# nRF_Board.net
KiCad netlist of a schematic drawn in Altium Designer
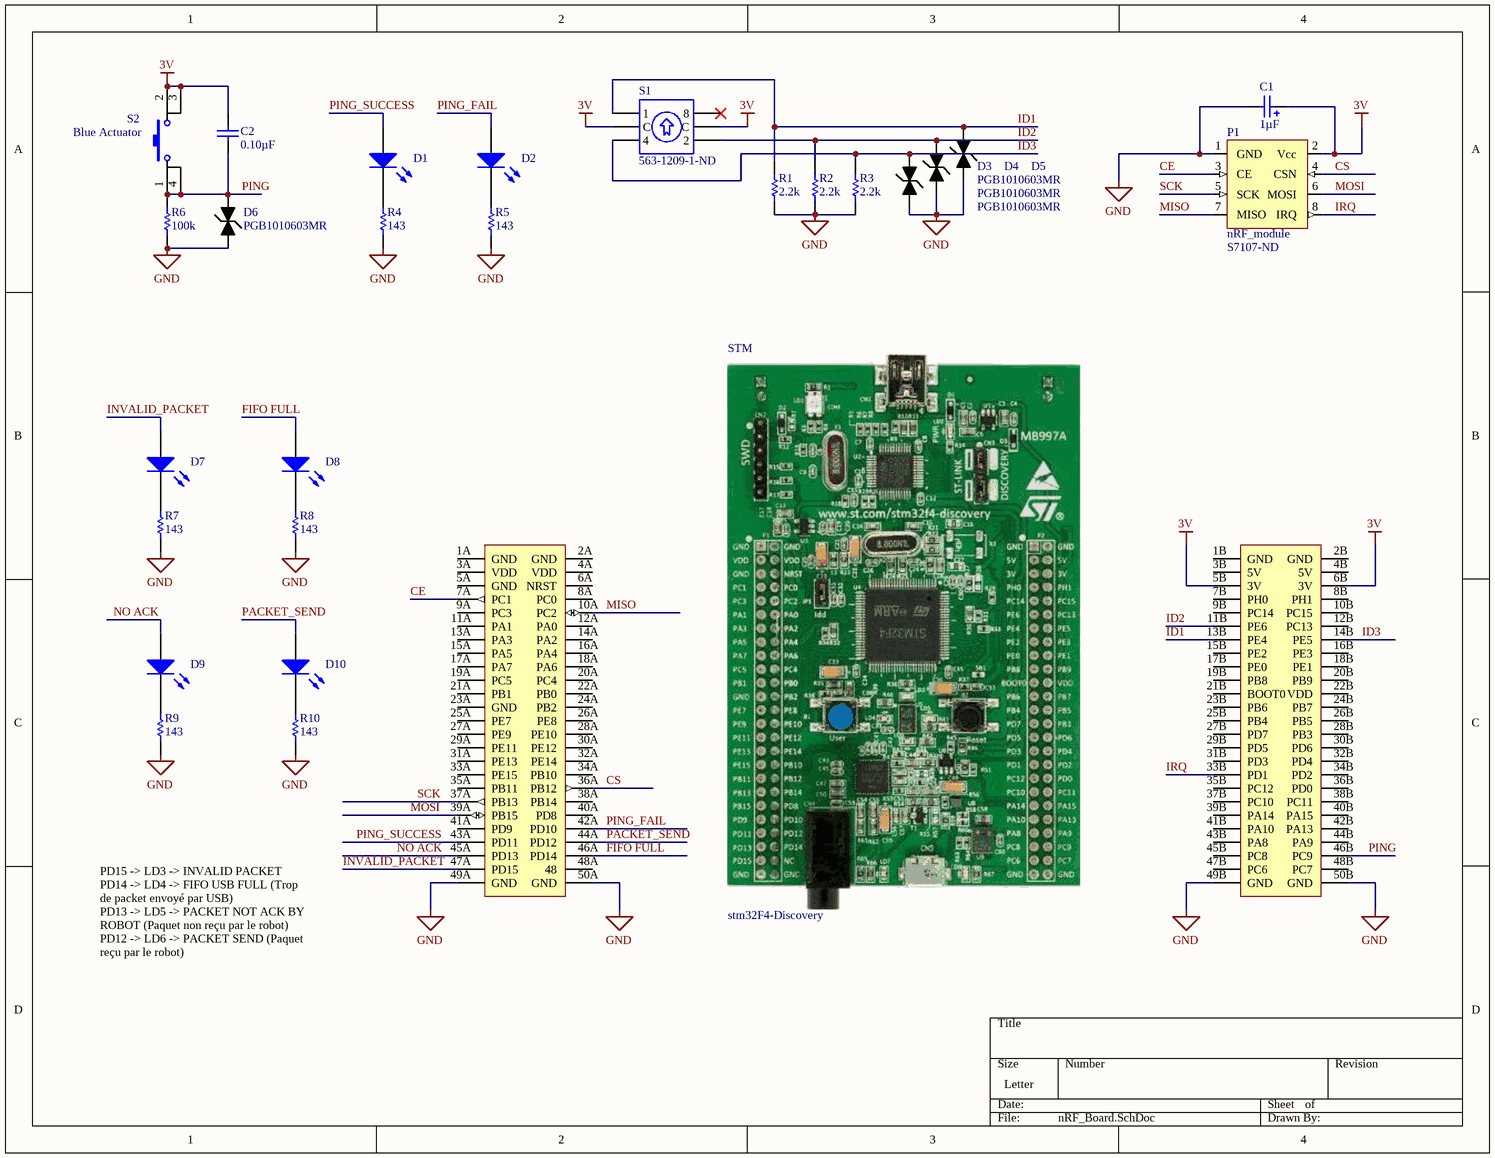
[diagram p0: nRF_Board.SchDoc]

(export (version "E")
  (design (tool "Eeschema 10.0.6"))
  (components
    (comp (ref "C1")
      (value "865060640001")
      (footprint "CAP 4.3x4.3mm")
      (description "CAP 1 UF 20% 50 V")
      (fields
        (field (name "MANUFACTURER") "Wurth Electronics Inc")
        (field (name "TOLERANCE") "±20%")
        (field (name "CAPACITANCE") "1µF")
      )
      (libsource (lib "ResCap") (part "865060640001"))
    )
    (comp (ref "C2")
      (value "CL10B104KB8SFNC")
      (footprint "0603")
      (description "CAP CER 0.1UF 50V X7R 0603")
      (fields
        (field (name "MANUFACTURER") "Samsung Electro-Mechanics America, Inc.")
        (field (name "TOLERANCE") "±10%")
        (field (name "CAPACITANCE") "0.10µF")
      )
      (libsource (lib "ResCap") (part "CL10B104KB8SFNC"))
    )
    (comp (ref "D1")
      (value "LG R971-KN-1")
      (footprint "0805")
      (description "LED GREEN DIFFUSED 0805 SMD")
      (fields (field (name "MANUFACTURER") "OSRAM Opto Semiconductors Inc."))
      (libsource (lib "MainBoard") (part "LG R971-KN-1"))
    )
    (comp (ref "D2")
      (value "LG R971-KN-1")
      (footprint "0805")
      (description "LED GREEN DIFFUSED 0805 SMD")
      (fields (field (name "MANUFACTURER") "OSRAM Opto Semiconductors Inc."))
      (libsource (lib "MainBoard") (part "LG R971-KN-1"))
    )
    (comp (ref "D3")
      (value "PGB1010603MR")
      (footprint "0603")
      (description "TVS DIODE 24VWM 150VC 0603")
      (libsource (lib "MainBoard") (part "PGB1010603MR"))
    )
    (comp (ref "D4")
      (value "PGB1010603MR")
      (footprint "0603")
      (description "TVS DIODE 24VWM 150VC 0603")
      (libsource (lib "MainBoard") (part "PGB1010603MR"))
    )
    (comp (ref "D5")
      (value "PGB1010603MR")
      (footprint "0603")
      (description "TVS DIODE 24VWM 150VC 0603")
      (libsource (lib "MainBoard") (part "PGB1010603MR"))
    )
    (comp (ref "D6")
      (value "PGB1010603MR")
      (footprint "0603")
      (description "TVS DIODE 24VWM 150VC 0603")
      (libsource (lib "MainBoard") (part "PGB1010603MR"))
    )
    (comp (ref "D7")
      (value "LG R971-KN-1")
      (footprint "0805")
      (description "LED GREEN DIFFUSED 0805 SMD")
      (fields (field (name "MANUFACTURER") "OSRAM Opto Semiconductors Inc."))
      (libsource (lib "MainBoard") (part "LG R971-KN-1"))
    )
    (comp (ref "D8")
      (value "LG R971-KN-1")
      (footprint "0805")
      (description "LED GREEN DIFFUSED 0805 SMD")
      (fields (field (name "MANUFACTURER") "OSRAM Opto Semiconductors Inc."))
      (libsource (lib "MainBoard") (part "LG R971-KN-1"))
    )
    (comp (ref "D9")
      (value "LG R971-KN-1")
      (footprint "0805")
      (description "LED GREEN DIFFUSED 0805 SMD")
      (fields (field (name "MANUFACTURER") "OSRAM Opto Semiconductors Inc."))
      (libsource (lib "MainBoard") (part "LG R971-KN-1"))
    )
    (comp (ref "D10")
      (value "LG R971-KN-1")
      (footprint "0805")
      (description "LED GREEN DIFFUSED 0805 SMD")
      (fields (field (name "MANUFACTURER") "OSRAM Opto Semiconductors Inc."))
      (libsource (lib "MainBoard") (part "LG R971-KN-1"))
    )
    (comp (ref "P1")
      (value "nRF_module")
      (footprint "nRF_connector")
      (description "2x4 100mil header")
      (fields (field (name "SUPPLIER PART NUMBER 1") "S7107-ND"))
      (libsource (lib "MainBoard") (part "nRF_module"))
    )
    (comp (ref "R1")
      (value "RC0603FR-072K2L")
      (footprint "0603")
      (description "RES SMD 2.2K OHM 1% 1/10W 0603")
      (fields
        (field (name "MANUFACTURER") "Yageo")
        (field (name "TOLERANCE") "±1%")
        (field (name "RESISTANCE (OHMS)") "2.2k")
      )
      (libsource (lib "ResCap") (part "RC0603FR-072K2L"))
    )
    (comp (ref "R2")
      (value "RC0603FR-072K2L")
      (footprint "0603")
      (description "RES SMD 2.2K OHM 1% 1/10W 0603")
      (fields
        (field (name "MANUFACTURER") "Yageo")
        (field (name "TOLERANCE") "±1%")
        (field (name "RESISTANCE (OHMS)") "2.2k")
      )
      (libsource (lib "ResCap") (part "RC0603FR-072K2L"))
    )
    (comp (ref "R3")
      (value "RC0603FR-072K2L")
      (footprint "0603")
      (description "RES SMD 2.2K OHM 1% 1/10W 0603")
      (fields
        (field (name "MANUFACTURER") "Yageo")
        (field (name "TOLERANCE") "±1%")
        (field (name "RESISTANCE (OHMS)") "2.2k")
      )
      (libsource (lib "ResCap") (part "RC0603FR-072K2L"))
    )
    (comp (ref "R4")
      (value "RC0603FR-07143RL")
      (footprint "0603")
      (description "RES SMD 143 OHM 1% 1/10W 0603")
      (fields
        (field (name "MANUFACTURER") "Yageo")
        (field (name "TOLERANCE") "±1%")
        (field (name "RESISTANCE (OHMS)") "143")
      )
      (libsource (lib "ResCap") (part "RC0603FR-07143RL"))
    )
    (comp (ref "R5")
      (value "RC0603FR-07143RL")
      (footprint "0603")
      (description "RES SMD 143 OHM 1% 1/10W 0603")
      (fields
        (field (name "MANUFACTURER") "Yageo")
        (field (name "TOLERANCE") "±1%")
        (field (name "RESISTANCE (OHMS)") "143")
      )
      (libsource (lib "ResCap") (part "RC0603FR-07143RL"))
    )
    (comp (ref "R6")
      (value "RC0603JR-07100KL")
      (footprint "0603")
      (description "RES SMD 100K OHM 5% 1/10W 0603")
      (fields
        (field (name "MANUFACTURER") "Yageo")
        (field (name "TOLERANCE") "±5%")
        (field (name "RESISTANCE (OHMS)") "100k")
      )
      (libsource (lib "ResCap") (part "RC0603JR-07100KL"))
    )
    (comp (ref "R7")
      (value "RC0603FR-07143RL")
      (footprint "0603")
      (description "RES SMD 143 OHM 1% 1/10W 0603")
      (fields
        (field (name "MANUFACTURER") "Yageo")
        (field (name "TOLERANCE") "±1%")
        (field (name "RESISTANCE (OHMS)") "143")
      )
      (libsource (lib "ResCap") (part "RC0603FR-07143RL"))
    )
    (comp (ref "R8")
      (value "RC0603FR-07143RL")
      (footprint "0603")
      (description "RES SMD 143 OHM 1% 1/10W 0603")
      (fields
        (field (name "MANUFACTURER") "Yageo")
        (field (name "TOLERANCE") "±1%")
        (field (name "RESISTANCE (OHMS)") "143")
      )
      (libsource (lib "ResCap") (part "RC0603FR-07143RL"))
    )
    (comp (ref "R9")
      (value "RC0603FR-07143RL")
      (footprint "0603")
      (description "RES SMD 143 OHM 1% 1/10W 0603")
      (fields
        (field (name "MANUFACTURER") "Yageo")
        (field (name "TOLERANCE") "±1%")
        (field (name "RESISTANCE (OHMS)") "143")
      )
      (libsource (lib "ResCap") (part "RC0603FR-07143RL"))
    )
    (comp (ref "R10")
      (value "RC0603FR-07143RL")
      (footprint "0603")
      (description "RES SMD 143 OHM 1% 1/10W 0603")
      (fields
        (field (name "MANUFACTURER") "Yageo")
        (field (name "TOLERANCE") "±1%")
        (field (name "RESISTANCE (OHMS)") "143")
      )
      (libsource (lib "ResCap") (part "RC0603FR-07143RL"))
    )
    (comp (ref "S1")
      (value "SH-7010TB")
      (footprint "RotarySwitch")
      (description "SWITCH ROTARY DIP BCD 100MA 5V")
      (fields
        (field (name "MANUFACTURER") "Copal Electronics Inc.")
        (field (name "SUPPLIER PART NUMBER 1") "563-1209-1-ND")
      )
      (libsource (lib "MainBoard") (part "SH-7010TB"))
    )
    (comp (ref "S2")
      (value "PTS645SM43SMTR92 LFS")
      (footprint "6 mm Tact Switches")
      (description "SWITCH TACTILE SPST-NO 0.05A 12V")
      (fields (field (name "MANUFACTURER") "C&K Components") (field (name "FEATURES") "Blue Actuator"))
      (libsource (lib "design3") (part "PTS645SM43SMTR92 LFS"))
    )
    (comp (ref "STM")
      (value "stm32F4-Discovery")
      (footprint "stm32-discovery")
      (libsource (lib "DesignIII") (part "stm32F4-Discovery"))
    )
  )
  (nets
    (net (code "1") (name "/CE") (class "Default")
      (node (ref "P1") (pin "3") (pinfunction "CE_3") (pintype "input"))
      (node (ref "STM") (pin "7A") (pinfunction "PC1_7A") (pintype "output"))
    )
    (net (code "2") (name "/CS") (class "Default")
      (node (ref "P1") (pin "4") (pinfunction "CSN_4") (pintype "input"))
      (node (ref "STM") (pin "36A") (pinfunction "PB12_36A") (pintype "output"))
    )
    (net (code "3") (name "/FIFO FULL") (class "Default")
      (node (ref "D8") (pin "1") (pinfunction "A_1") (pintype "passive"))
      (node (ref "STM") (pin "46A") (pinfunction "PD14_46A") (pintype "passive"))
    )
    (net (code "4") (name "/ID1") (class "Default")
      (node (ref "D3") (pin "2") (pintype "passive"))
      (node (ref "R1") (pin "2") (pinfunction "2_2") (pintype "passive"))
      (node (ref "S1") (pin "1") (pinfunction "1_1") (pintype "passive"))
      (node (ref "STM") (pin "13B") (pinfunction "PE4_13B") (pintype "passive"))
    )
    (net (code "5") (name "/ID2") (class "Default")
      (node (ref "D5") (pin "2") (pintype "passive"))
      (node (ref "R2") (pin "2") (pinfunction "2_2") (pintype "passive"))
      (node (ref "S1") (pin "4") (pinfunction "2_4") (pintype "passive"))
      (node (ref "STM") (pin "11B") (pinfunction "PE6_11B") (pintype "passive"))
    )
    (net (code "6") (name "/ID3") (class "Default")
      (node (ref "D4") (pin "2") (pintype "passive"))
      (node (ref "R3") (pin "2") (pinfunction "2_2") (pintype "passive"))
      (node (ref "S1") (pin "3") (pinfunction "4_3") (pintype "passive"))
      (node (ref "STM") (pin "14B") (pinfunction "PE5_14B") (pintype "passive"))
    )
    (net (code "7") (name "/INVALID_PACKET") (class "Default")
      (node (ref "D7") (pin "1") (pinfunction "A_1") (pintype "passive"))
      (node (ref "STM") (pin "47A") (pinfunction "PD15_47A") (pintype "passive"))
    )
    (net (code "8") (name "/IRQ") (class "Default")
      (node (ref "P1") (pin "8") (pinfunction "IRQ_8") (pintype "output"))
      (node (ref "STM") (pin "33B") (pinfunction "PD1_33B") (pintype "passive"))
    )
    (net (code "9") (name "/MISO") (class "Default")
      (node (ref "P1") (pin "7") (pinfunction "MISO_7") (pintype "bidirectional"))
      (node (ref "STM") (pin "10A") (pinfunction "PC2_10A") (pintype "bidirectional"))
    )
    (net (code "10") (name "/MOSI") (class "Default")
      (node (ref "P1") (pin "6") (pinfunction "MOSI_6") (pintype "bidirectional"))
      (node (ref "STM") (pin "39A") (pinfunction "PB15_39A") (pintype "bidirectional"))
    )
    (net (code "11") (name "/NO ACK") (class "Default")
      (node (ref "D9") (pin "1") (pinfunction "A_1") (pintype "passive"))
      (node (ref "STM") (pin "45A") (pinfunction "PD13_45A") (pintype "passive"))
    )
    (net (code "12") (name "/PACKET_SEND") (class "Default")
      (node (ref "D10") (pin "1") (pinfunction "A_1") (pintype "passive"))
      (node (ref "STM") (pin "44A") (pinfunction "PD12_44A") (pintype "passive"))
    )
    (net (code "13") (name "/PING") (class "Default")
      (node (ref "C2") (pin "1") (pinfunction "1_1") (pintype "passive"))
      (node (ref "D6") (pin "2") (pintype "passive"))
      (node (ref "R6") (pin "2") (pinfunction "2_2") (pintype "passive"))
      (node (ref "S2") (pin "1") (pinfunction "1_1") (pintype "passive"))
      (node (ref "S2") (pin "4") (pinfunction "4_4") (pintype "passive"))
      (node (ref "STM") (pin "46B") (pinfunction "PC9_46B") (pintype "passive"))
    )
    (net (code "14") (name "/PING_FAIL") (class "Default")
      (node (ref "D2") (pin "1") (pinfunction "A_1") (pintype "passive"))
      (node (ref "STM") (pin "42A") (pinfunction "PD10_42A") (pintype "passive"))
    )
    (net (code "15") (name "/PING_SUCCESS") (class "Default")
      (node (ref "D1") (pin "1") (pinfunction "A_1") (pintype "passive"))
      (node (ref "STM") (pin "43A") (pinfunction "PD11_43A") (pintype "passive"))
    )
    (net (code "16") (name "/SCK") (class "Default")
      (node (ref "P1") (pin "5") (pinfunction "SCK_5") (pintype "input"))
      (node (ref "STM") (pin "37A") (pinfunction "PB13_37A") (pintype "output"))
    )
    (net (code "17") (name "3V") (class "Default")
      (node (ref "C1") (pin "1") (pinfunction "1_1") (pintype "passive"))
      (node (ref "C2") (pin "2") (pinfunction "2_2") (pintype "passive"))
      (node (ref "P1") (pin "2") (pinfunction "Vcc_2") (pintype "power_in"))
      (node (ref "S1") (pin "2") (pinfunction "C_2") (pintype "passive"))
      (node (ref "S1") (pin "5") (pinfunction "C_5") (pintype "passive"))
      (node (ref "S2") (pin "2") (pinfunction "2_2") (pintype "passive"))
      (node (ref "S2") (pin "3") (pinfunction "3_3") (pintype "passive"))
      (node (ref "STM") (pin "5B") (pinfunction "3V_5B") (pintype "passive"))
      (node (ref "STM") (pin "6B") (pinfunction "3V_6B") (pintype "passive"))
    )
    (net (code "18") (name "GND") (class "Default")
      (node (ref "C1") (pin "2") (pinfunction "2_2") (pintype "passive"))
      (node (ref "D3") (pin "1") (pintype "passive"))
      (node (ref "D4") (pin "1") (pintype "passive"))
      (node (ref "D5") (pin "1") (pintype "passive"))
      (node (ref "D6") (pin "1") (pintype "passive"))
      (node (ref "P1") (pin "1") (pinfunction "GND_1") (pintype "power_in"))
      (node (ref "R1") (pin "1") (pinfunction "1_1") (pintype "passive"))
      (node (ref "R10") (pin "1") (pinfunction "1_1") (pintype "passive"))
      (node (ref "R2") (pin "1") (pinfunction "1_1") (pintype "passive"))
      (node (ref "R3") (pin "1") (pinfunction "1_1") (pintype "passive"))
      (node (ref "R4") (pin "1") (pinfunction "1_1") (pintype "passive"))
      (node (ref "R5") (pin "1") (pinfunction "1_1") (pintype "passive"))
      (node (ref "R6") (pin "1") (pinfunction "1_1") (pintype "passive"))
      (node (ref "R7") (pin "1") (pinfunction "1_1") (pintype "passive"))
      (node (ref "R8") (pin "1") (pinfunction "1_1") (pintype "passive"))
      (node (ref "R9") (pin "1") (pinfunction "1_1") (pintype "passive"))
      (node (ref "STM") (pin "49A") (pinfunction "GND_49A") (pintype "passive"))
      (node (ref "STM") (pin "49B") (pinfunction "GND_49B") (pintype "passive"))
      (node (ref "STM") (pin "50A") (pinfunction "GND_50A") (pintype "passive"))
      (node (ref "STM") (pin "50B") (pinfunction "GND_50B") (pintype "passive"))
    )
    (net (code "19") (name "Net-(D1-K)") (class "Default")
      (node (ref "D1") (pin "2") (pinfunction "K_2") (pintype "passive"))
      (node (ref "R4") (pin "2") (pinfunction "2_2") (pintype "passive"))
    )
    (net (code "20") (name "Net-(D2-K)") (class "Default")
      (node (ref "D2") (pin "2") (pinfunction "K_2") (pintype "passive"))
      (node (ref "R5") (pin "2") (pinfunction "2_2") (pintype "passive"))
    )
    (net (code "21") (name "Net-(D7-K)") (class "Default")
      (node (ref "D7") (pin "2") (pinfunction "K_2") (pintype "passive"))
      (node (ref "R7") (pin "2") (pinfunction "2_2") (pintype "passive"))
    )
    (net (code "22") (name "Net-(D8-K)") (class "Default")
      (node (ref "D8") (pin "2") (pinfunction "K_2") (pintype "passive"))
      (node (ref "R8") (pin "2") (pinfunction "2_2") (pintype "passive"))
    )
    (net (code "23") (name "Net-(D9-K)") (class "Default")
      (node (ref "D9") (pin "2") (pinfunction "K_2") (pintype "passive"))
      (node (ref "R9") (pin "2") (pinfunction "2_2") (pintype "passive"))
    )
    (net (code "24") (name "Net-(D10-K)") (class "Default")
      (node (ref "D10") (pin "2") (pinfunction "K_2") (pintype "passive"))
      (node (ref "R10") (pin "2") (pinfunction "2_2") (pintype "passive"))
    )
    (net (code "25") (name "unconnected-(S1-8-Pad6)") (class "Default")
      (node (ref "S1") (pin "6") (pinfunction "8_6") (pintype "passive+no_connect"))
    )
    (net (code "26") (name "unconnected-(STM-5V-Pad3B)") (class "Default")
      (node (ref "STM") (pin "3B") (pinfunction "5V_3B") (pintype "passive"))
    )
    (net (code "27") (name "unconnected-(STM-5V-Pad4B)") (class "Default")
      (node (ref "STM") (pin "4B") (pinfunction "5V_4B") (pintype "passive"))
    )
    (net (code "28") (name "unconnected-(STM-48-Pad48A)") (class "Default")
      (node (ref "STM") (pin "48A") (pinfunction "48_48A") (pintype "passive"))
    )
    (net (code "29") (name "unconnected-(STM-BOOT0-Pad21B)") (class "Default")
      (node (ref "STM") (pin "21B") (pinfunction "BOOT0_21B") (pintype "passive"))
    )
    (net (code "30") (name "unconnected-(STM-GND-Pad1A)") (class "Default")
      (node (ref "STM") (pin "1A") (pinfunction "GND_1A") (pintype "passive"))
    )
    (net (code "31") (name "unconnected-(STM-GND-Pad1B)") (class "Default")
      (node (ref "STM") (pin "1B") (pinfunction "GND_1B") (pintype "passive"))
    )
    (net (code "32") (name "unconnected-(STM-GND-Pad2A)") (class "Default")
      (node (ref "STM") (pin "2A") (pinfunction "GND_2A") (pintype "passive"))
    )
    (net (code "33") (name "unconnected-(STM-GND-Pad2B)") (class "Default")
      (node (ref "STM") (pin "2B") (pinfunction "GND_2B") (pintype "passive"))
    )
    (net (code "34") (name "unconnected-(STM-GND-Pad5A)") (class "Default")
      (node (ref "STM") (pin "5A") (pinfunction "GND_5A") (pintype "passive"))
    )
    (net (code "35") (name "unconnected-(STM-GND-Pad23A)") (class "Default")
      (node (ref "STM") (pin "23A") (pinfunction "GND_23A") (pintype "passive"))
    )
    (net (code "36") (name "unconnected-(STM-NRST-Pad6A)") (class "Default")
      (node (ref "STM") (pin "6A") (pinfunction "NRST_6A") (pintype "passive"))
    )
    (net (code "37") (name "unconnected-(STM-PA0-Pad12A)") (class "Default")
      (node (ref "STM") (pin "12A") (pinfunction "PA0_12A") (pintype "passive"))
    )
    (net (code "38") (name "unconnected-(STM-PA1-Pad11A)") (class "Default")
      (node (ref "STM") (pin "11A") (pinfunction "PA1_11A") (pintype "passive"))
    )
    (net (code "39") (name "unconnected-(STM-PA2-Pad14A)") (class "Default")
      (node (ref "STM") (pin "14A") (pinfunction "PA2_14A") (pintype "passive"))
    )
    (net (code "40") (name "unconnected-(STM-PA3-Pad13A)") (class "Default")
      (node (ref "STM") (pin "13A") (pinfunction "PA3_13A") (pintype "passive"))
    )
    (net (code "41") (name "unconnected-(STM-PA4-Pad16A)") (class "Default")
      (node (ref "STM") (pin "16A") (pinfunction "PA4_16A") (pintype "passive"))
    )
    (net (code "42") (name "unconnected-(STM-PA5-Pad15A)") (class "Default")
      (node (ref "STM") (pin "15A") (pinfunction "PA5_15A") (pintype "passive"))
    )
    (net (code "43") (name "unconnected-(STM-PA6-Pad18A)") (class "Default")
      (node (ref "STM") (pin "18A") (pinfunction "PA6_18A") (pintype "passive"))
    )
    (net (code "44") (name "unconnected-(STM-PA7-Pad17A)") (class "Default")
      (node (ref "STM") (pin "17A") (pinfunction "PA7_17A") (pintype "passive"))
    )
    (net (code "45") (name "unconnected-(STM-PA8-Pad43B)") (class "Default")
      (node (ref "STM") (pin "43B") (pinfunction "PA8_43B") (pintype "passive"))
    )
    (net (code "46") (name "unconnected-(STM-PA9-Pad44B)") (class "Default")
      (node (ref "STM") (pin "44B") (pinfunction "PA9_44B") (pintype "passive"))
    )
    (net (code "47") (name "unconnected-(STM-PA10-Pad41B)") (class "Default")
      (node (ref "STM") (pin "41B") (pinfunction "PA10_41B") (pintype "passive"))
    )
    (net (code "48") (name "unconnected-(STM-PA13-Pad42B)") (class "Default")
      (node (ref "STM") (pin "42B") (pinfunction "PA13_42B") (pintype "passive"))
    )
    (net (code "49") (name "unconnected-(STM-PA14-Pad39B)") (class "Default")
      (node (ref "STM") (pin "39B") (pinfunction "PA14_39B") (pintype "passive"))
    )
    (net (code "50") (name "unconnected-(STM-PA15-Pad40B)") (class "Default")
      (node (ref "STM") (pin "40B") (pinfunction "PA15_40B") (pintype "passive"))
    )
    (net (code "51") (name "unconnected-(STM-PB0-Pad22A)") (class "Default")
      (node (ref "STM") (pin "22A") (pinfunction "PB0_22A") (pintype "passive"))
    )
    (net (code "52") (name "unconnected-(STM-PB1-Pad21A)") (class "Default")
      (node (ref "STM") (pin "21A") (pinfunction "PB1_21A") (pintype "passive"))
    )
    (net (code "53") (name "unconnected-(STM-PB2-Pad24A)") (class "Default")
      (node (ref "STM") (pin "24A") (pinfunction "PB2_24A") (pintype "passive"))
    )
    (net (code "54") (name "unconnected-(STM-PB3-Pad28B)") (class "Default")
      (node (ref "STM") (pin "28B") (pinfunction "PB3_28B") (pintype "passive"))
    )
    (net (code "55") (name "unconnected-(STM-PB4-Pad25B)") (class "Default")
      (node (ref "STM") (pin "25B") (pinfunction "PB4_25B") (pintype "passive"))
    )
    (net (code "56") (name "unconnected-(STM-PB5-Pad26B)") (class "Default")
      (node (ref "STM") (pin "26B") (pinfunction "PB5_26B") (pintype "passive"))
    )
    (net (code "57") (name "unconnected-(STM-PB6-Pad23B)") (class "Default")
      (node (ref "STM") (pin "23B") (pinfunction "PB6_23B") (pintype "passive"))
    )
    (net (code "58") (name "unconnected-(STM-PB7-Pad24B)") (class "Default")
      (node (ref "STM") (pin "24B") (pinfunction "PB7_24B") (pintype "passive"))
    )
    (net (code "59") (name "unconnected-(STM-PB8-Pad19B)") (class "Default")
      (node (ref "STM") (pin "19B") (pinfunction "PB8_19B") (pintype "passive"))
    )
    (net (code "60") (name "unconnected-(STM-PB9-Pad20B)") (class "Default")
      (node (ref "STM") (pin "20B") (pinfunction "PB9_20B") (pintype "passive"))
    )
    (net (code "61") (name "unconnected-(STM-PB10-Pad34A)") (class "Default")
      (node (ref "STM") (pin "34A") (pinfunction "PB10_34A") (pintype "passive"))
    )
    (net (code "62") (name "unconnected-(STM-PB11-Pad35A)") (class "Default")
      (node (ref "STM") (pin "35A") (pinfunction "PB11_35A") (pintype "passive"))
    )
    (net (code "63") (name "unconnected-(STM-PB14-Pad38A)") (class "Default")
      (node (ref "STM") (pin "38A") (pinfunction "PB14_38A") (pintype "passive"))
    )
    (net (code "64") (name "unconnected-(STM-PC0-Pad8A)") (class "Default")
      (node (ref "STM") (pin "8A") (pinfunction "PC0_8A") (pintype "passive"))
    )
    (net (code "65") (name "unconnected-(STM-PC3-Pad9A)") (class "Default")
      (node (ref "STM") (pin "9A") (pinfunction "PC3_9A") (pintype "passive"))
    )
    (net (code "66") (name "unconnected-(STM-PC4-Pad20A)") (class "Default")
      (node (ref "STM") (pin "20A") (pinfunction "PC4_20A") (pintype "passive"))
    )
    (net (code "67") (name "unconnected-(STM-PC5-Pad19A)") (class "Default")
      (node (ref "STM") (pin "19A") (pinfunction "PC5_19A") (pintype "passive"))
    )
    (net (code "68") (name "unconnected-(STM-PC6-Pad47B)") (class "Default")
      (node (ref "STM") (pin "47B") (pinfunction "PC6_47B") (pintype "passive"))
    )
    (net (code "69") (name "unconnected-(STM-PC7-Pad48B)") (class "Default")
      (node (ref "STM") (pin "48B") (pinfunction "PC7_48B") (pintype "passive"))
    )
    (net (code "70") (name "unconnected-(STM-PC8-Pad45B)") (class "Default")
      (node (ref "STM") (pin "45B") (pinfunction "PC8_45B") (pintype "passive"))
    )
    (net (code "71") (name "unconnected-(STM-PC10-Pad37B)") (class "Default")
      (node (ref "STM") (pin "37B") (pinfunction "PC10_37B") (pintype "passive"))
    )
    (net (code "72") (name "unconnected-(STM-PC11-Pad38B)") (class "Default")
      (node (ref "STM") (pin "38B") (pinfunction "PC11_38B") (pintype "passive"))
    )
    (net (code "73") (name "unconnected-(STM-PC12-Pad35B)") (class "Default")
      (node (ref "STM") (pin "35B") (pinfunction "PC12_35B") (pintype "passive"))
    )
    (net (code "74") (name "unconnected-(STM-PC13-Pad12B)") (class "Default")
      (node (ref "STM") (pin "12B") (pinfunction "PC13_12B") (pintype "passive"))
    )
    (net (code "75") (name "unconnected-(STM-PC14-Pad9B)") (class "Default")
      (node (ref "STM") (pin "9B") (pinfunction "PC14_9B") (pintype "passive"))
    )
    (net (code "76") (name "unconnected-(STM-PC15-Pad10B)") (class "Default")
      (node (ref "STM") (pin "10B") (pinfunction "PC15_10B") (pintype "passive"))
    )
    (net (code "77") (name "unconnected-(STM-PD0-Pad36B)") (class "Default")
      (node (ref "STM") (pin "36B") (pinfunction "PD0_36B") (pintype "passive"))
    )
    (net (code "78") (name "unconnected-(STM-PD2-Pad34B)") (class "Default")
      (node (ref "STM") (pin "34B") (pinfunction "PD2_34B") (pintype "passive"))
    )
    (net (code "79") (name "unconnected-(STM-PD3-Pad31B)") (class "Default")
      (node (ref "STM") (pin "31B") (pinfunction "PD3_31B") (pintype "passive"))
    )
    (net (code "80") (name "unconnected-(STM-PD4-Pad32B)") (class "Default")
      (node (ref "STM") (pin "32B") (pinfunction "PD4_32B") (pintype "passive"))
    )
    (net (code "81") (name "unconnected-(STM-PD5-Pad29B)") (class "Default")
      (node (ref "STM") (pin "29B") (pinfunction "PD5_29B") (pintype "passive"))
    )
    (net (code "82") (name "unconnected-(STM-PD6-Pad30B)") (class "Default")
      (node (ref "STM") (pin "30B") (pinfunction "PD6_30B") (pintype "passive"))
    )
    (net (code "83") (name "unconnected-(STM-PD7-Pad27B)") (class "Default")
      (node (ref "STM") (pin "27B") (pinfunction "PD7_27B") (pintype "passive"))
    )
    (net (code "84") (name "unconnected-(STM-PD8-Pad40A)") (class "Default")
      (node (ref "STM") (pin "40A") (pinfunction "PD8_40A") (pintype "passive"))
    )
    (net (code "85") (name "unconnected-(STM-PD9-Pad41A)") (class "Default")
      (node (ref "STM") (pin "41A") (pinfunction "PD9_41A") (pintype "passive"))
    )
    (net (code "86") (name "unconnected-(STM-PE0-Pad17B)") (class "Default")
      (node (ref "STM") (pin "17B") (pinfunction "PE0_17B") (pintype "passive"))
    )
    (net (code "87") (name "unconnected-(STM-PE1-Pad18B)") (class "Default")
      (node (ref "STM") (pin "18B") (pinfunction "PE1_18B") (pintype "passive"))
    )
    (net (code "88") (name "unconnected-(STM-PE2-Pad15B)") (class "Default")
      (node (ref "STM") (pin "15B") (pinfunction "PE2_15B") (pintype "passive"))
    )
    (net (code "89") (name "unconnected-(STM-PE3-Pad16B)") (class "Default")
      (node (ref "STM") (pin "16B") (pinfunction "PE3_16B") (pintype "passive"))
    )
    (net (code "90") (name "unconnected-(STM-PE7-Pad25A)") (class "Default")
      (node (ref "STM") (pin "25A") (pinfunction "PE7_25A") (pintype "passive"))
    )
    (net (code "91") (name "unconnected-(STM-PE8-Pad26A)") (class "Default")
      (node (ref "STM") (pin "26A") (pinfunction "PE8_26A") (pintype "passive"))
    )
    (net (code "92") (name "unconnected-(STM-PE9-Pad27A)") (class "Default")
      (node (ref "STM") (pin "27A") (pinfunction "PE9_27A") (pintype "passive"))
    )
    (net (code "93") (name "unconnected-(STM-PE10-Pad28A)") (class "Default")
      (node (ref "STM") (pin "28A") (pinfunction "PE10_28A") (pintype "passive"))
    )
    (net (code "94") (name "unconnected-(STM-PE11-Pad29A)") (class "Default")
      (node (ref "STM") (pin "29A") (pinfunction "PE11_29A") (pintype "passive"))
    )
    (net (code "95") (name "unconnected-(STM-PE12-Pad30A)") (class "Default")
      (node (ref "STM") (pin "30A") (pinfunction "PE12_30A") (pintype "passive"))
    )
    (net (code "96") (name "unconnected-(STM-PE13-Pad31A)") (class "Default")
      (node (ref "STM") (pin "31A") (pinfunction "PE13_31A") (pintype "passive"))
    )
    (net (code "97") (name "unconnected-(STM-PE14-Pad32A)") (class "Default")
      (node (ref "STM") (pin "32A") (pinfunction "PE14_32A") (pintype "passive"))
    )
    (net (code "98") (name "unconnected-(STM-PE15-Pad33A)") (class "Default")
      (node (ref "STM") (pin "33A") (pinfunction "PE15_33A") (pintype "passive"))
    )
    (net (code "99") (name "unconnected-(STM-PH0-Pad7B)") (class "Default")
      (node (ref "STM") (pin "7B") (pinfunction "PH0_7B") (pintype "passive"))
    )
    (net (code "100") (name "unconnected-(STM-PH1-Pad8B)") (class "Default")
      (node (ref "STM") (pin "8B") (pinfunction "PH1_8B") (pintype "passive"))
    )
    (net (code "101") (name "unconnected-(STM-VDD-Pad3A)") (class "Default")
      (node (ref "STM") (pin "3A") (pinfunction "VDD_3A") (pintype "passive"))
    )
    (net (code "102") (name "unconnected-(STM-VDD-Pad4A)") (class "Default")
      (node (ref "STM") (pin "4A") (pinfunction "VDD_4A") (pintype "passive"))
    )
    (net (code "103") (name "unconnected-(STM-VDD-Pad22B)") (class "Default")
      (node (ref "STM") (pin "22B") (pinfunction "VDD_22B") (pintype "passive"))
    )
  )
)
